# 5V_LS.net
KiCad netlist of a schematic drawn in Altium Designer
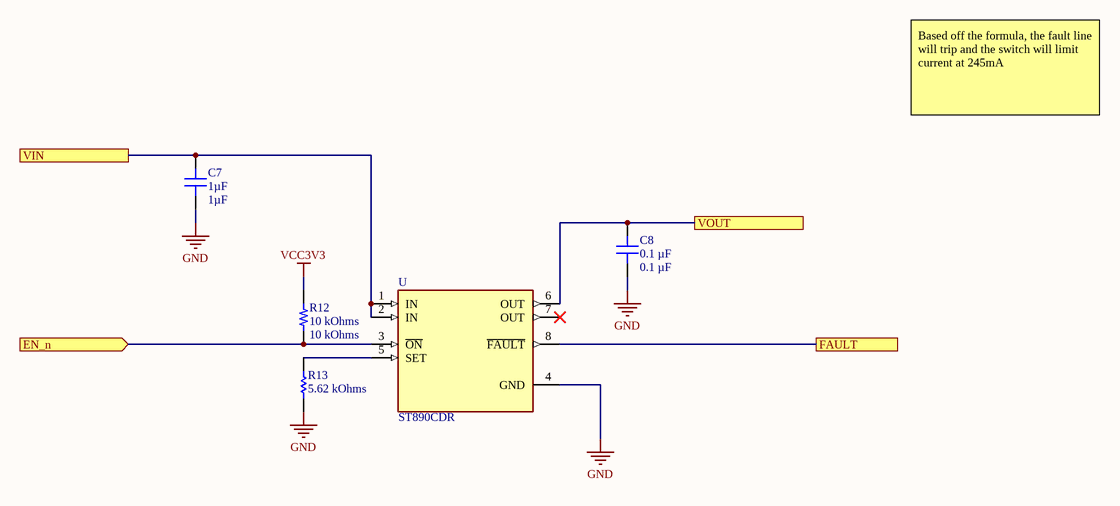
[diagram p0: 5V_LS.SchDoc]

(export (version "E")
  (design (tool "Eeschema 10.0.6"))
  (components
    (comp (ref "C7")
      (value "1µF")
      (footprint "CAP 0805_2012")
      (description "CAP CER 1UF 10V X7R 0805")
      (fields (field (name "PART NUMBER") "MM05ZC105KCZ2A") (field (name "ALTIUM_VALUE") "1µF"))
      (libsource (lib "Celestial Altium Library - altium_library") (part "Capacitor"))
    )
    (comp (ref "C8")
      (value "0.1 µF")
      (footprint "CAP 0805_2012")
      (description "CAP CER 0.1UF 50V X7R 0805")
      (fields (field (name "PART NUMBER") "CC0805MRX7R9BB104") (field (name "ALTIUM_VALUE") "0.1 µF"))
      (libsource (lib "Celestial Altium Library - altium_library") (part "Capacitor"))
    )
    (comp (ref "R12")
      (value "10 kOhms")
      (footprint "RES 0805_2012")
      (description "RES 10K OHM 0.1% 1/10W 0805")
      (fields (field (name "PART NUMBER") "RNCS0805BKE10K0") (field (name "ALTIUM_VALUE") "10 kOhms"))
      (libsource (lib "Celestial Altium Library - altium_library") (part "Resistor"))
    )
    (comp (ref "R13")
      (value "5.62 kOhms")
      (footprint "RESC2013X60X40ML20T25")
      (fields (field (name "PART NUMBER") "ERA6AEB5621V") (field (name "MANUFACTURER") "Panasonic"))
      (libsource (lib "Altium Content Vault") (part "RES"))
    )
    (comp (ref "U")
      (value "ST890CDR")
      (footprint "SOIC127P600X175-8N")
      (description "Power Switch/Driver 1:1 P-Channel 1.2A 8-SO")
      (fields (field (name "MF") "STMicroelectronics"))
      (libsource (lib "ST890CDR") (part "ST890CDR"))
    )
  )
  (nets
    (net (code "1") (name "/EN_n") (class "Default")
      (node (ref "R12") (pin "1") (pinfunction "1_1") (pintype "passive"))
      (node (ref "U") (pin "3") (pinfunction "~{ON}_3") (pintype "input"))
    )
    (net (code "2") (name "/FAULT") (class "Default")
      (node (ref "U") (pin "8") (pinfunction "~{FAULT}_8") (pintype "output"))
    )
    (net (code "3") (name "/VIN") (class "Default")
      (node (ref "C7") (pin "2") (pinfunction "2_2") (pintype "passive"))
      (node (ref "U") (pin "1") (pinfunction "IN_1") (pintype "input"))
      (node (ref "U") (pin "2") (pinfunction "IN_2") (pintype "input"))
    )
    (net (code "4") (name "/VOUT") (class "Default")
      (node (ref "C8") (pin "2") (pinfunction "2_2") (pintype "passive"))
      (node (ref "U") (pin "6") (pinfunction "OUT_6") (pintype "output"))
    )
    (net (code "5") (name "GND") (class "Default")
      (node (ref "C7") (pin "1") (pinfunction "1_1") (pintype "passive"))
      (node (ref "C8") (pin "1") (pinfunction "1_1") (pintype "passive"))
      (node (ref "R13") (pin "1") (pinfunction "1_1") (pintype "passive"))
      (node (ref "U") (pin "4") (pinfunction "GND_4") (pintype "power_in"))
    )
    (net (code "6") (name "Net-(U-SET)") (class "Default")
      (node (ref "R13") (pin "2") (pinfunction "2_2") (pintype "passive"))
      (node (ref "U") (pin "5") (pinfunction "SET_5") (pintype "input"))
    )
    (net (code "7") (name "VCC3V3") (class "Default")
      (node (ref "R12") (pin "2") (pinfunction "2_2") (pintype "passive"))
    )
    (net (code "8") (name "unconnected-(U-OUT-Pad7)") (class "Default")
      (node (ref "U") (pin "7") (pinfunction "OUT_7") (pintype "output+no_connect"))
    )
  )
)
